# DispenserV2_0.net
KiCad netlist of a schematic drawn in EAGLE
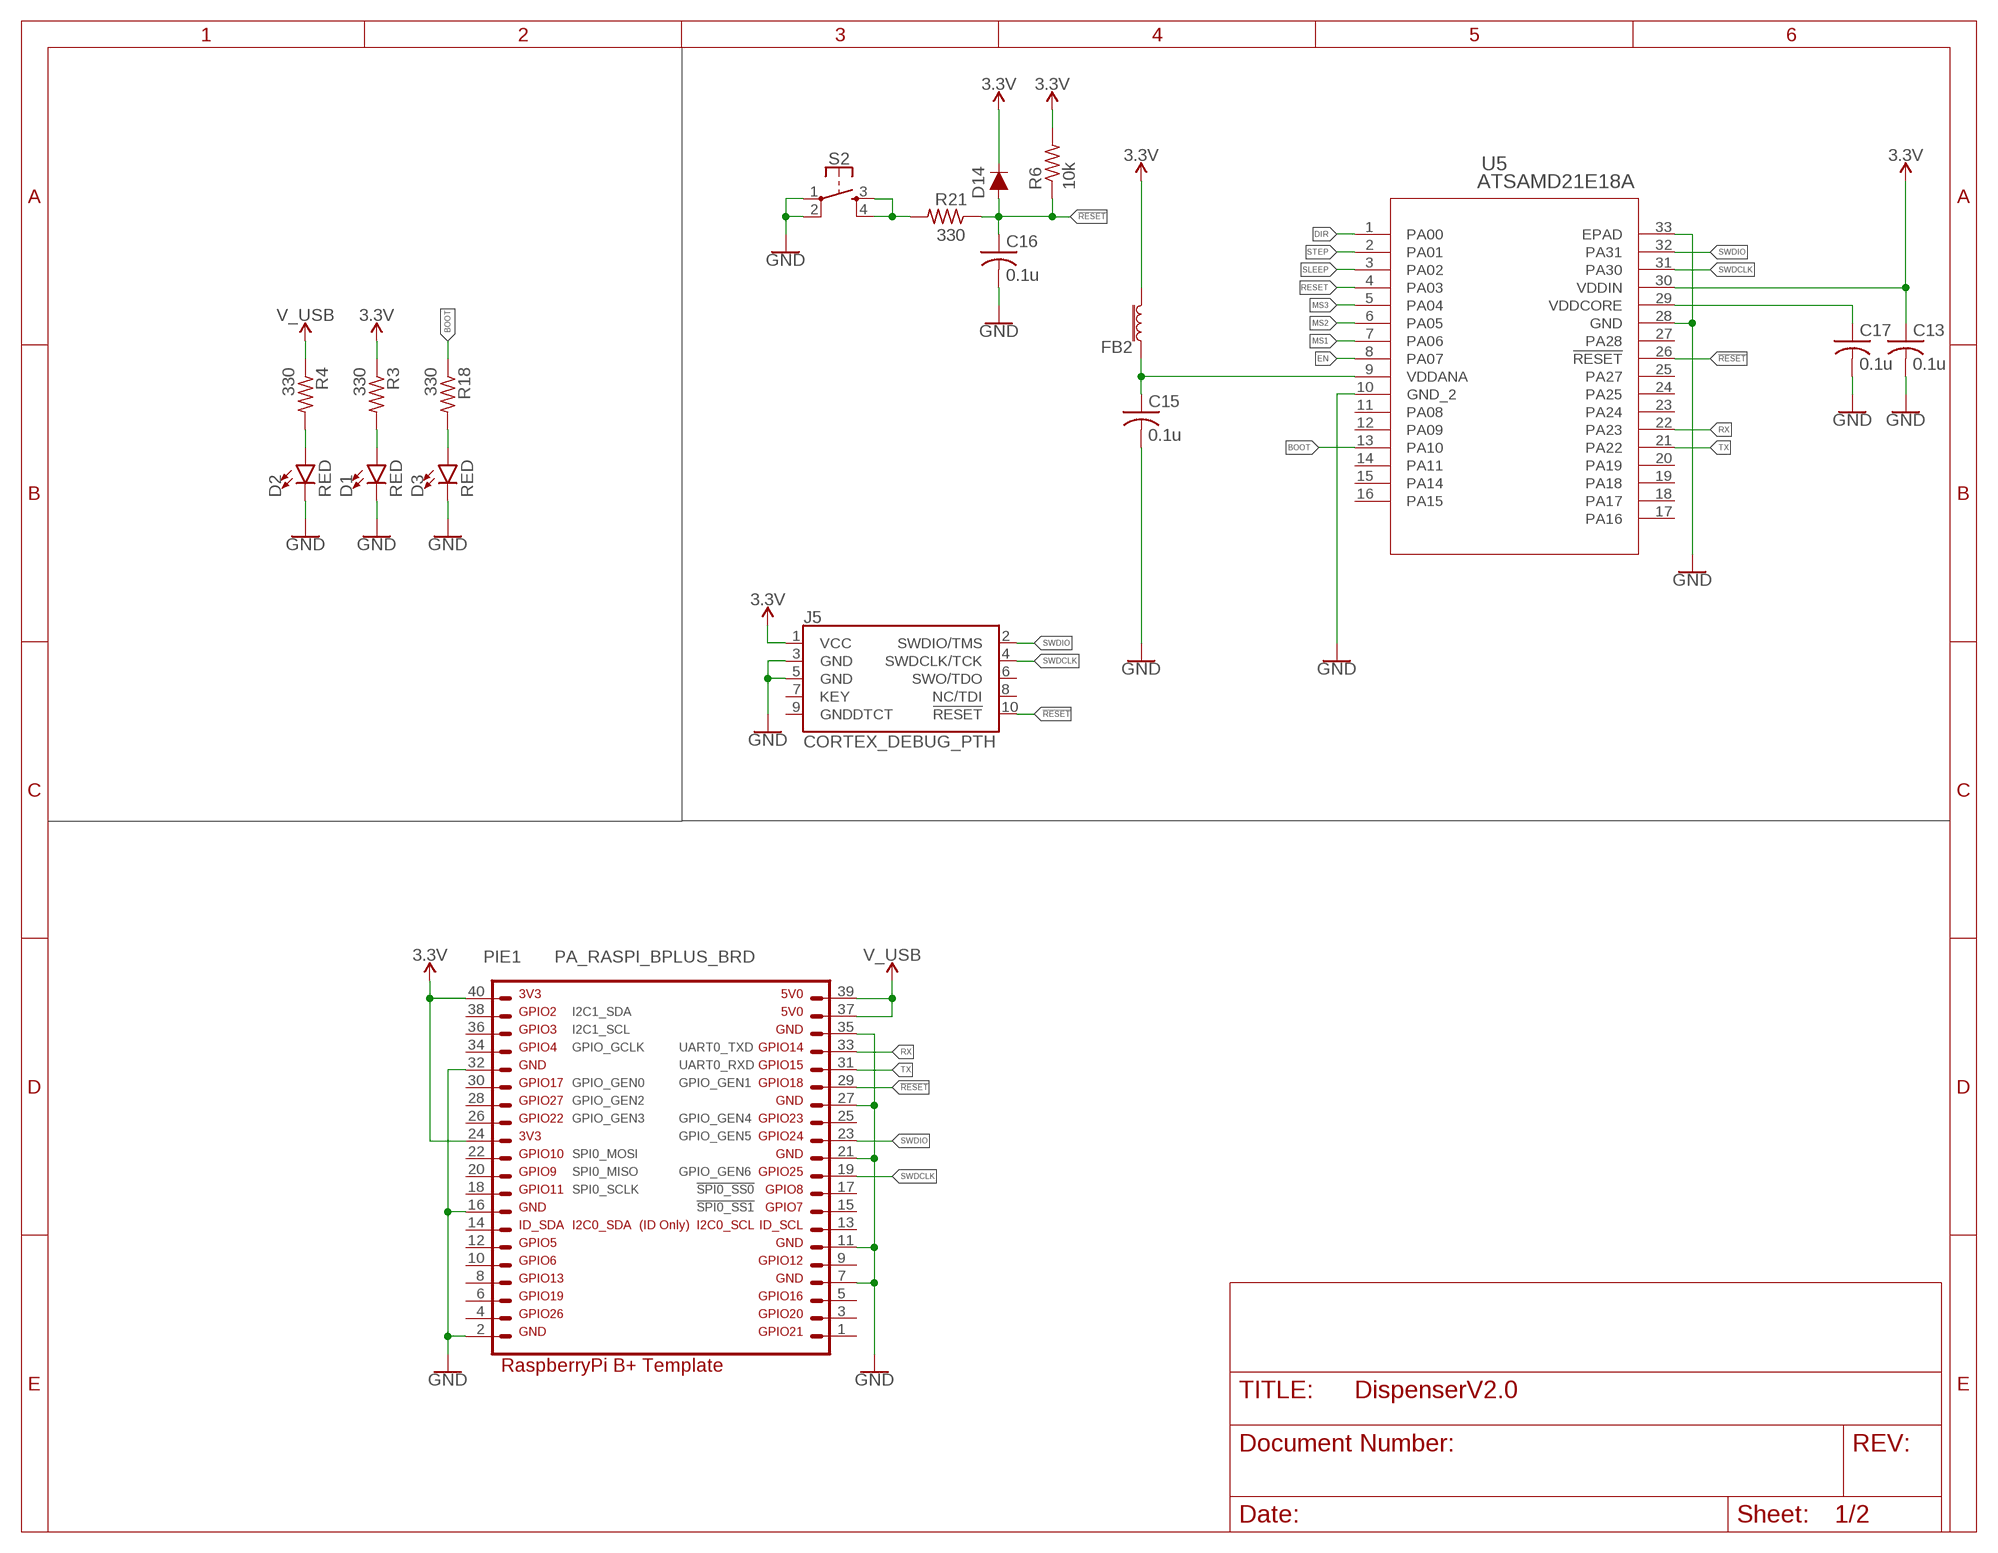
[diagram p0: schematic, sheet 1]
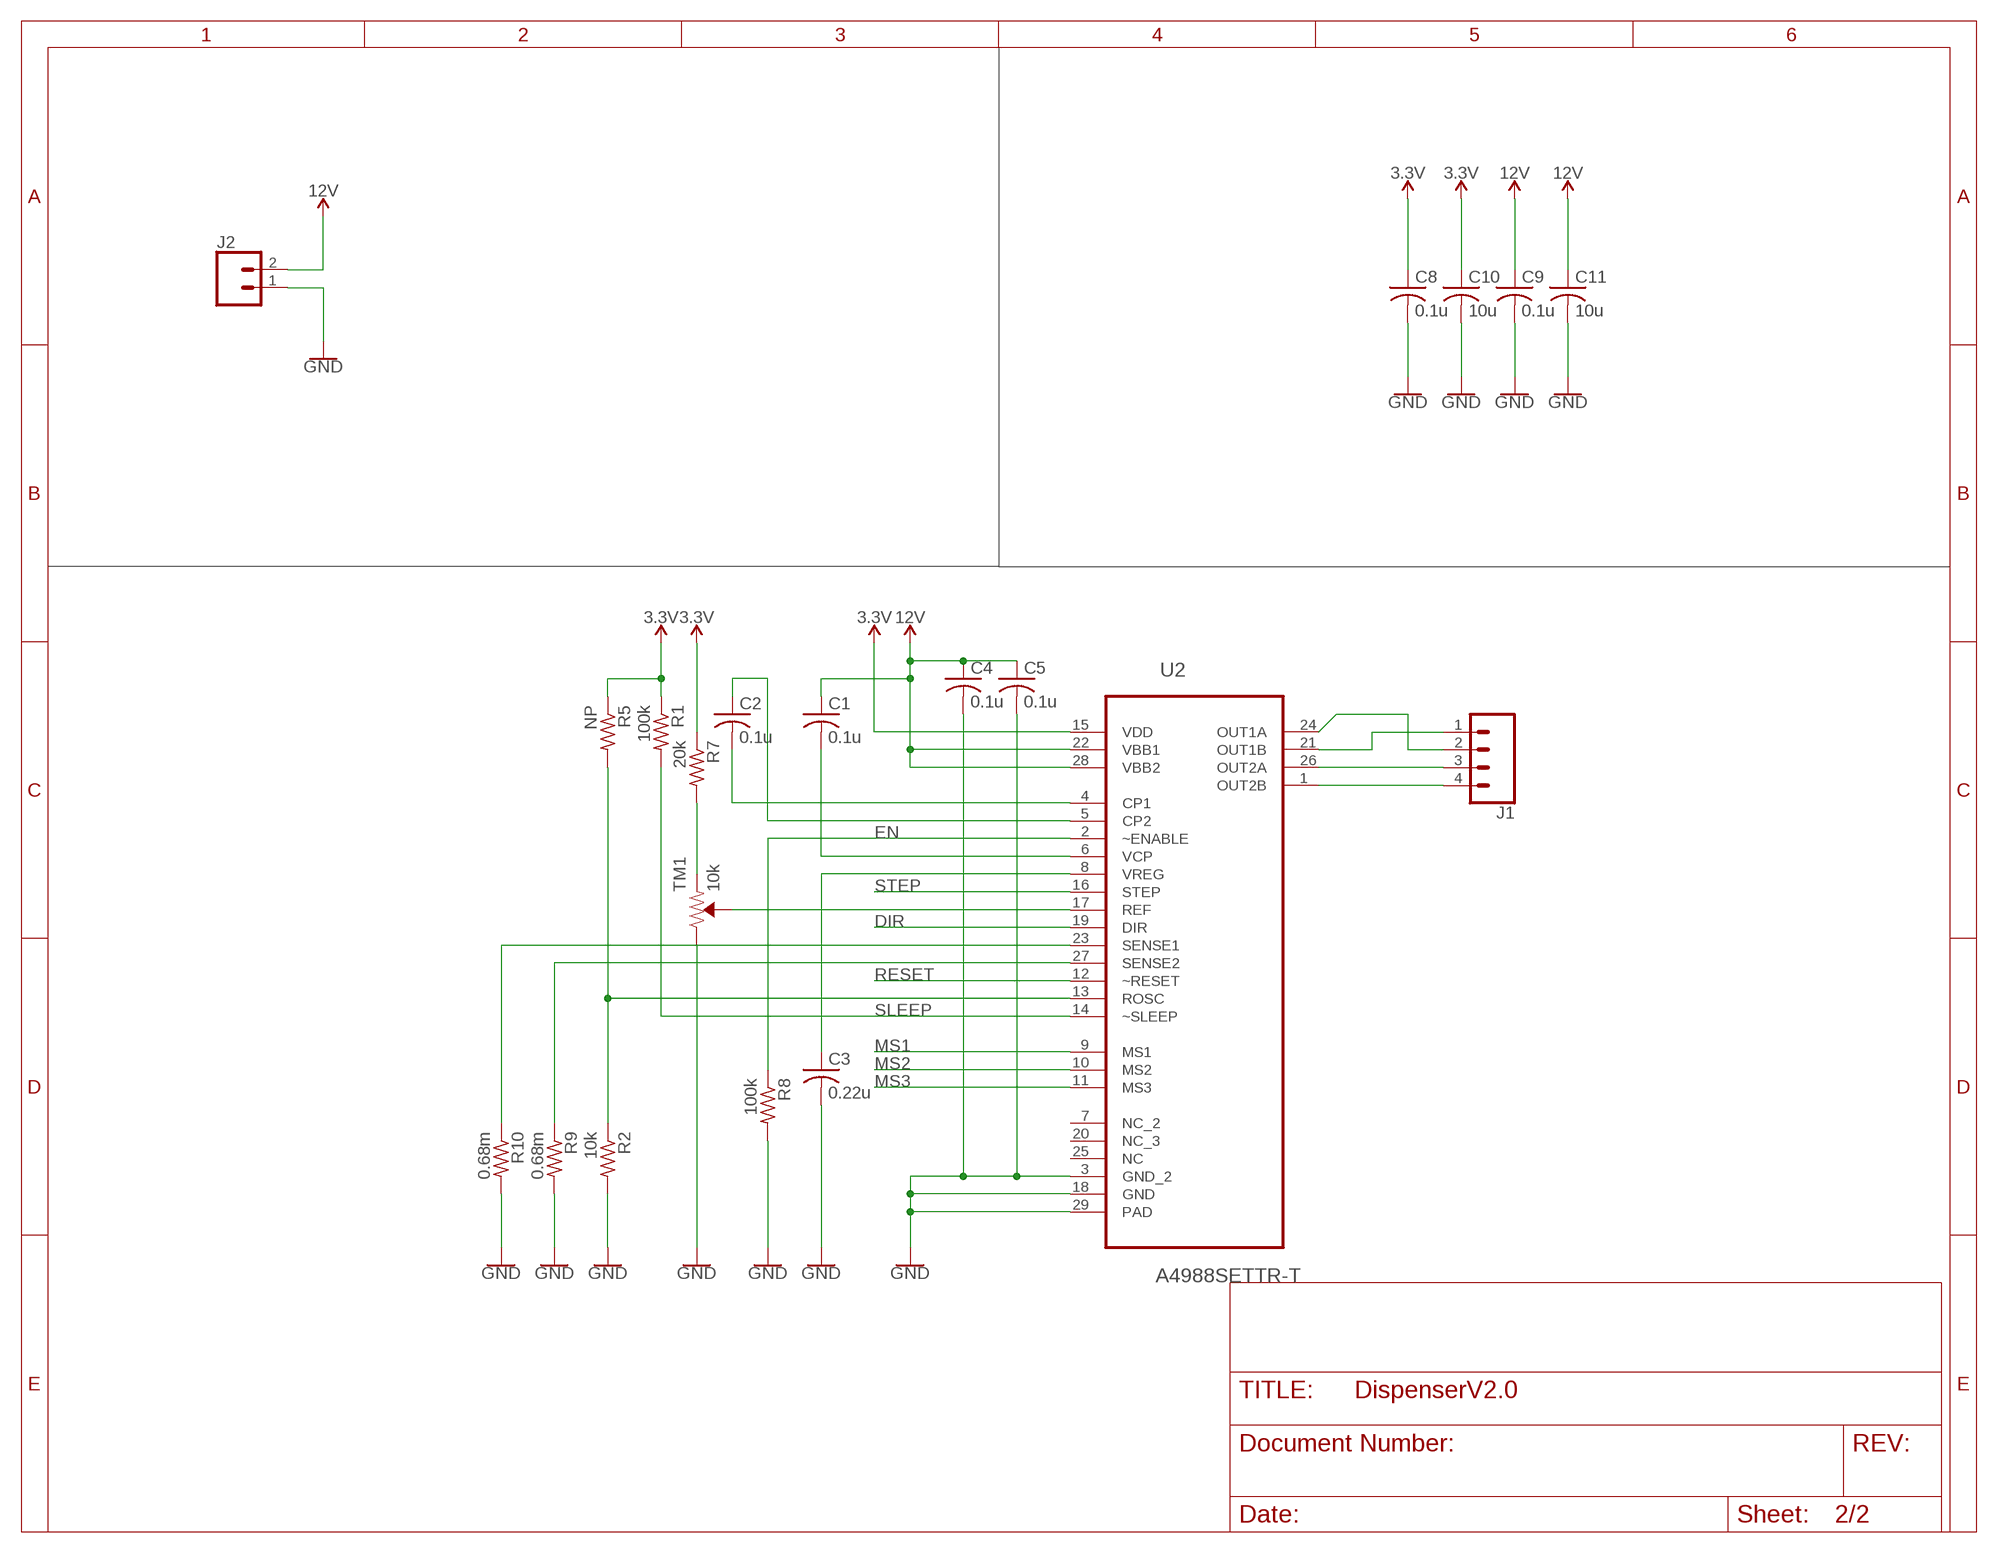
[diagram p1: schematic, sheet 2]

(export (version "E")
  (design (tool "Eeschema 10.0.6"))
  (components
    (comp (ref "C1")
      (value "0.1u")
      (footprint "eagle-import:C0402")
      (libsource (lib "eagle-import") (part "C-USC0402"))
    )
    (comp (ref "C2")
      (value "0.1u")
      (footprint "eagle-import:C0402")
      (libsource (lib "eagle-import") (part "C-USC0402"))
    )
    (comp (ref "C3")
      (value "0.22u")
      (footprint "eagle-import:C0402")
      (libsource (lib "eagle-import") (part "C-USC0402"))
    )
    (comp (ref "C4")
      (value "0.1u")
      (footprint "eagle-import:C0402")
      (libsource (lib "eagle-import") (part "C-USC0402"))
    )
    (comp (ref "C5")
      (value "0.1u")
      (footprint "eagle-import:C0402")
      (libsource (lib "eagle-import") (part "C-USC0402"))
    )
    (comp (ref "C8")
      (value "0.1u")
      (footprint "eagle-import:C0603")
      (libsource (lib "eagle-import") (part "adafruit_420_C-USC0603"))
    )
    (comp (ref "C9")
      (value "0.1u")
      (footprint "eagle-import:C0603")
      (libsource (lib "eagle-import") (part "adafruit_420_C-USC0603"))
    )
    (comp (ref "C10")
      (value "10u")
      (footprint "eagle-import:C1206")
      (libsource (lib "eagle-import") (part "C-USC1206"))
    )
    (comp (ref "C11")
      (value "10u")
      (footprint "eagle-import:C1206")
      (libsource (lib "eagle-import") (part "C-USC1206"))
    )
    (comp (ref "J1")
      (value "CONN_04")
      (footprint "eagle-import:1X04")
      (libsource (lib "eagle-import") (part "CONN_04"))
    )
    (comp (ref "J2")
      (value "CONN_023.5MM")
      (footprint "eagle-import:SCREWTERMINAL-3.5MM-2")
      (libsource (lib "eagle-import") (part "CONN_023.5MM"))
    )
    (comp (ref "R1")
      (value "100k")
      (footprint "eagle-import:R0402")
      (libsource (lib "eagle-import") (part "R-US_R0402"))
    )
    (comp (ref "R2")
      (value "10k")
      (footprint "eagle-import:R0402")
      (libsource (lib "eagle-import") (part "R-US_R0402"))
    )
    (comp (ref "R5")
      (value "NP")
      (footprint "eagle-import:R0402")
      (libsource (lib "eagle-import") (part "R-US_R0402"))
    )
    (comp (ref "R7")
      (value "20k")
      (footprint "eagle-import:R0402")
      (libsource (lib "eagle-import") (part "R-US_R0402"))
    )
    (comp (ref "R8")
      (value "100k")
      (footprint "eagle-import:R0402")
      (libsource (lib "eagle-import") (part "R-US_R0402"))
    )
    (comp (ref "R9")
      (value "0.68m")
      (footprint "eagle-import:R0805")
      (libsource (lib "eagle-import") (part "R-US_R0805"))
    )
    (comp (ref "R10")
      (value "0.68m")
      (footprint "eagle-import:R0805")
      (libsource (lib "eagle-import") (part "R-US_R0805"))
    )
    (comp (ref "TM1")
      (value "10k")
      (footprint "eagle-import:TRIMPOT-SMD-TC33X")
      (libsource (lib "eagle-import") (part "TRIMPOT-SMD-3MM-OPEN-1/10W-25%"))
    )
    (comp (ref "U2")
      (value "A4988SETTR-T")
      (footprint "eagle-import:QFN50P500X500X100-29N")
      (fields (field (name "MF") "Allegro MicroSystems LLC") (field (name "MP") "A4988SETTRT"))
      (libsource (lib "eagle-import") (part "A4988SETTR-T"))
    )
    (comp (ref "C13")
      (value "0.1u")
      (footprint "eagle-import:C0603K")
      (libsource (lib "eagle-import") (part "C-USC0603K"))
    )
    (comp (ref "C15")
      (value "0.1u")
      (footprint "eagle-import:C0603K")
      (libsource (lib "eagle-import") (part "C-USC0603K"))
    )
    (comp (ref "C16")
      (value "0.1u")
      (footprint "eagle-import:C0603K")
      (libsource (lib "eagle-import") (part "C-USC0603K"))
    )
    (comp (ref "C17")
      (value "0.1u")
      (footprint "eagle-import:C0603K")
      (libsource (lib "eagle-import") (part "C-USC0603K"))
    )
    (comp (ref "D1")
      (value "RED")
      (footprint "eagle-import:LED-0603")
      (libsource (lib "eagle-import") (part "LED-RED0603"))
    )
    (comp (ref "D2")
      (value "RED")
      (footprint "eagle-import:LED-0603")
      (libsource (lib "eagle-import") (part "LED-RED0603"))
    )
    (comp (ref "D3")
      (value "RED")
      (footprint "eagle-import:LED-0603")
      (libsource (lib "eagle-import") (part "LED-RED0603"))
    )
    (comp (ref "D14")
      (value "250mA/100V")
      (footprint "eagle-import:SOD-323")
      (libsource (lib "eagle-import") (part "DIODE-BAS16J"))
    )
    (comp (ref "FB2")
      (value "30Ω/1.8A")
      (footprint "eagle-import:0603")
      (libsource (lib "eagle-import") (part "FERRITE_BEAD-0603"))
    )
    (comp (ref "J5")
      (value "CORTEX_DEBUG_PTH")
      (footprint "eagle-import:2X5-PTH-1.27MM")
      (libsource (lib "eagle-import") (part "CORTEX_DEBUG_PTH"))
    )
    (comp (ref "PIE1")
      (value "PA_RASPI_BPLUS_BRD")
      (footprint "eagle-import:PA_RASPI_PLATE_BPLUS")
      (libsource (lib "eagle-import") (part "PA_RASPI_BPLUS_BRD"))
    )
    (comp (ref "R3")
      (value "330")
      (footprint "eagle-import:R0603")
      (libsource (lib "eagle-import") (part "R-US_R0603"))
    )
    (comp (ref "R4")
      (value "330")
      (footprint "eagle-import:R0603")
      (libsource (lib "eagle-import") (part "R-US_R0603"))
    )
    (comp (ref "R6")
      (value "10k")
      (footprint "eagle-import:R0603")
      (libsource (lib "eagle-import") (part "R-US_R0603"))
    )
    (comp (ref "R18")
      (value "330")
      (footprint "eagle-import:R0603")
      (libsource (lib "eagle-import") (part "R-US_R0603"))
    )
    (comp (ref "R21")
      (value "330")
      (footprint "eagle-import:R0603")
      (libsource (lib "eagle-import") (part "R-US_R0603"))
    )
    (comp (ref "S2")
      (value "MOMENTARY-SWITCH-SPST-2-SMD-5.2MM")
      (footprint "eagle-import:TACTILE_SWITCH_SMD_5.2MM")
      (libsource (lib "eagle-import") (part "MOMENTARY-SWITCH-SPST-2-SMD-5.2MM"))
    )
    (comp (ref "U5")
      (value "ATSAMD21E18A")
      (footprint "eagle-import:QFN32_5X5MC")
      (fields
        (field (name "MANUFACTURER_PART_NUMBER") "ATSAMD21E18A-MUT")
        (field (name "COPYRIGHT") "Copyright (C) 2018 Accelerated Designs. All rights reserved")
      )
      (libsource (lib "eagle-import") (part "ATSAMD21E18A-MUT"))
    )
  )
  (nets
    (net (code "1") (name "3.3V") (class "Default")
      (node (ref "C10") (pin "1") (pinfunction "1_1") (pintype "passive"))
      (node (ref "C13") (pin "1") (pinfunction "1_1") (pintype "passive"))
      (node (ref "C8") (pin "1") (pinfunction "1_1") (pintype "passive"))
      (node (ref "D14") (pin "C") (pinfunction "C_C") (pintype "passive"))
      (node (ref "FB2") (pin "2") (pinfunction "2_2") (pintype "passive"))
      (node (ref "J5") (pin "1") (pinfunction "VCC_1") (pintype "bidirectional"))
      (node (ref "PIE1") (pin "24") (pinfunction "24_24") (pintype "passive"))
      (node (ref "PIE1") (pin "40") (pinfunction "40_40") (pintype "passive"))
      (node (ref "R1") (pin "1") (pinfunction "1_1") (pintype "passive"))
      (node (ref "R3") (pin "1") (pinfunction "1_1") (pintype "passive"))
      (node (ref "R5") (pin "1") (pinfunction "1_1") (pintype "passive"))
      (node (ref "R6") (pin "2") (pinfunction "2_2") (pintype "passive"))
      (node (ref "R7") (pin "1") (pinfunction "1_1") (pintype "passive"))
      (node (ref "U2") (pin "15") (pinfunction "VDD_15") (pintype "power_in"))
      (node (ref "U5") (pin "30") (pinfunction "VDDIN_30") (pintype "power_in"))
    )
    (net (code "2") (name "12V") (class "Default")
      (node (ref "C1") (pin "1") (pinfunction "1_1") (pintype "passive"))
      (node (ref "C11") (pin "1") (pinfunction "1_1") (pintype "passive"))
      (node (ref "C4") (pin "1") (pinfunction "1_1") (pintype "passive"))
      (node (ref "C5") (pin "1") (pinfunction "1_1") (pintype "passive"))
      (node (ref "C9") (pin "1") (pinfunction "1_1") (pintype "passive"))
      (node (ref "J2") (pin "2") (pinfunction "2_2") (pintype "passive"))
      (node (ref "U2") (pin "22") (pinfunction "VBB1_22") (pintype "power_in"))
      (node (ref "U2") (pin "28") (pinfunction "VBB2_28") (pintype "power_in"))
    )
    (net (code "3") (name "BOOT") (class "Default")
      (node (ref "R18") (pin "1") (pinfunction "1_1") (pintype "passive"))
      (node (ref "U5") (pin "13") (pinfunction "PA10_13") (pintype "bidirectional"))
    )
    (net (code "4") (name "DIR") (class "Default")
      (node (ref "U2") (pin "19") (pinfunction "DIR_19") (pintype "input"))
      (node (ref "U5") (pin "1") (pinfunction "PA00_1") (pintype "bidirectional"))
    )
    (net (code "5") (name "EN") (class "Default")
      (node (ref "R8") (pin "1") (pinfunction "1_1") (pintype "passive"))
      (node (ref "U2") (pin "2") (pinfunction "~{ENABLE}_2") (pintype "input"))
      (node (ref "U5") (pin "8") (pinfunction "PA07_8") (pintype "bidirectional"))
    )
    (net (code "6") (name "GND") (class "Default")
      (node (ref "C10") (pin "2") (pinfunction "2_2") (pintype "passive"))
      (node (ref "C11") (pin "2") (pinfunction "2_2") (pintype "passive"))
      (node (ref "C13") (pin "2") (pinfunction "2_2") (pintype "passive"))
      (node (ref "C15") (pin "2") (pinfunction "2_2") (pintype "passive"))
      (node (ref "C16") (pin "2") (pinfunction "2_2") (pintype "passive"))
      (node (ref "C17") (pin "2") (pinfunction "2_2") (pintype "passive"))
      (node (ref "C3") (pin "2") (pinfunction "2_2") (pintype "passive"))
      (node (ref "C4") (pin "2") (pinfunction "2_2") (pintype "passive"))
      (node (ref "C5") (pin "2") (pinfunction "2_2") (pintype "passive"))
      (node (ref "C8") (pin "2") (pinfunction "2_2") (pintype "passive"))
      (node (ref "C9") (pin "2") (pinfunction "2_2") (pintype "passive"))
      (node (ref "D1") (pin "C") (pinfunction "C_C") (pintype "passive"))
      (node (ref "D2") (pin "C") (pinfunction "C_C") (pintype "passive"))
      (node (ref "D3") (pin "C") (pinfunction "C_C") (pintype "passive"))
      (node (ref "J2") (pin "1") (pinfunction "1_1") (pintype "passive"))
      (node (ref "J5") (pin "3") (pinfunction "GND_3") (pintype "bidirectional"))
      (node (ref "J5") (pin "5") (pinfunction "GND_5") (pintype "bidirectional"))
      (node (ref "PIE1") (pin "11") (pinfunction "11_11") (pintype "passive"))
      (node (ref "PIE1") (pin "16") (pinfunction "16_16") (pintype "passive"))
      (node (ref "PIE1") (pin "2") (pinfunction "2_2") (pintype "passive"))
      (node (ref "PIE1") (pin "21") (pinfunction "21_21") (pintype "passive"))
      (node (ref "PIE1") (pin "27") (pinfunction "27_27") (pintype "passive"))
      (node (ref "PIE1") (pin "32") (pinfunction "32_32") (pintype "passive"))
      (node (ref "PIE1") (pin "35") (pinfunction "35_35") (pintype "passive"))
      (node (ref "PIE1") (pin "7") (pinfunction "7_7") (pintype "passive"))
      (node (ref "R10") (pin "2") (pinfunction "2_2") (pintype "passive"))
      (node (ref "R2") (pin "2") (pinfunction "2_2") (pintype "passive"))
      (node (ref "R8") (pin "2") (pinfunction "2_2") (pintype "passive"))
      (node (ref "R9") (pin "2") (pinfunction "2_2") (pintype "passive"))
      (node (ref "S2") (pin "1") (pinfunction "1_1") (pintype "passive"))
      (node (ref "S2") (pin "2") (pinfunction "2_2") (pintype "passive"))
      (node (ref "TM1") (pin "1") (pinfunction "CW_1") (pintype "passive"))
      (node (ref "U2") (pin "18") (pinfunction "GND_18") (pintype "passive"))
      (node (ref "U2") (pin "29") (pinfunction "PAD_29") (pintype "passive"))
      (node (ref "U2") (pin "3") (pinfunction "GND_2_3") (pintype "passive"))
      (node (ref "U5") (pin "10") (pinfunction "GND_2_10") (pintype "passive"))
      (node (ref "U5") (pin "28") (pinfunction "GND_28") (pintype "passive"))
      (node (ref "U5") (pin "33") (pinfunction "EPAD_33") (pintype "passive"))
    )
    (net (code "7") (name "MS1") (class "Default")
      (node (ref "U2") (pin "9") (pinfunction "MS1_9") (pintype "input"))
      (node (ref "U5") (pin "7") (pinfunction "PA06_7") (pintype "bidirectional"))
    )
    (net (code "8") (name "MS2") (class "Default")
      (node (ref "U2") (pin "10") (pinfunction "MS2_10") (pintype "input"))
      (node (ref "U5") (pin "6") (pinfunction "PA05_6") (pintype "bidirectional"))
    )
    (net (code "9") (name "MS3") (class "Default")
      (node (ref "U2") (pin "11") (pinfunction "MS3_11") (pintype "input"))
      (node (ref "U5") (pin "5") (pinfunction "PA04_5") (pintype "bidirectional"))
    )
    (net (code "10") (name "Net-(D1-PadA)") (class "Default")
      (node (ref "D1") (pin "A") (pinfunction "A_A") (pintype "passive"))
      (node (ref "R3") (pin "2") (pinfunction "2_2") (pintype "passive"))
    )
    (net (code "11") (name "Net-(D2-PadA)") (class "Default")
      (node (ref "D2") (pin "A") (pinfunction "A_A") (pintype "passive"))
      (node (ref "R4") (pin "2") (pinfunction "2_2") (pintype "passive"))
    )
    (net (code "12") (name "Net-(D3-PadA)") (class "Default")
      (node (ref "D3") (pin "A") (pinfunction "A_A") (pintype "passive"))
      (node (ref "R18") (pin "2") (pinfunction "2_2") (pintype "passive"))
    )
    (net (code "13") (name "Net-(R21-Pad2)") (class "Default")
      (node (ref "R21") (pin "2") (pinfunction "2_2") (pintype "passive"))
      (node (ref "S2") (pin "3") (pinfunction "3_3") (pintype "passive"))
      (node (ref "S2") (pin "4") (pinfunction "4_4") (pintype "passive"))
    )
    (net (code "14") (name "Net-(TM1-CCW)") (class "Default")
      (node (ref "R7") (pin "2") (pinfunction "2_2") (pintype "passive"))
      (node (ref "TM1") (pin "3") (pinfunction "CCW_3") (pintype "passive"))
    )
    (net (code "15") (name "Net-(TM1-WIPER)") (class "Default")
      (node (ref "TM1") (pin "2") (pinfunction "WIPER_2") (pintype "passive"))
      (node (ref "U2") (pin "17") (pinfunction "REF_17") (pintype "input"))
    )
    (net (code "16") (name "Net-(U2-CP1)") (class "Default")
      (node (ref "C2") (pin "2") (pinfunction "2_2") (pintype "passive"))
      (node (ref "U2") (pin "4") (pinfunction "CP1_4") (pintype "passive"))
    )
    (net (code "17") (name "Net-(U2-CP2)") (class "Default")
      (node (ref "C2") (pin "1") (pinfunction "1_1") (pintype "passive"))
      (node (ref "U2") (pin "5") (pinfunction "CP2_5") (pintype "passive"))
    )
    (net (code "18") (name "Net-(U2-OUT1A)") (class "Default")
      (node (ref "J1") (pin "2") (pinfunction "2_2") (pintype "passive"))
      (node (ref "U2") (pin "24") (pinfunction "OUT1A_24") (pintype "output"))
    )
    (net (code "19") (name "Net-(U2-OUT1B)") (class "Default")
      (node (ref "J1") (pin "1") (pinfunction "1_1") (pintype "passive"))
      (node (ref "U2") (pin "21") (pinfunction "OUT1B_21") (pintype "output"))
    )
    (net (code "20") (name "Net-(U2-OUT2A)") (class "Default")
      (node (ref "J1") (pin "3") (pinfunction "3_3") (pintype "passive"))
      (node (ref "U2") (pin "26") (pinfunction "OUT2A_26") (pintype "output"))
    )
    (net (code "21") (name "Net-(U2-OUT2B)") (class "Default")
      (node (ref "J1") (pin "4") (pinfunction "4_4") (pintype "passive"))
      (node (ref "U2") (pin "1") (pinfunction "OUT2B_1") (pintype "output"))
    )
    (net (code "22") (name "Net-(U2-ROSC)") (class "Default")
      (node (ref "R2") (pin "1") (pinfunction "1_1") (pintype "passive"))
      (node (ref "R5") (pin "2") (pinfunction "2_2") (pintype "passive"))
      (node (ref "U2") (pin "13") (pinfunction "ROSC_13") (pintype "input"))
    )
    (net (code "23") (name "Net-(U2-SENSE1)") (class "Default")
      (node (ref "R10") (pin "1") (pinfunction "1_1") (pintype "passive"))
      (node (ref "U2") (pin "23") (pinfunction "SENSE1_23") (pintype "input"))
    )
    (net (code "24") (name "Net-(U2-SENSE2)") (class "Default")
      (node (ref "R9") (pin "1") (pinfunction "1_1") (pintype "passive"))
      (node (ref "U2") (pin "27") (pinfunction "SENSE2_27") (pintype "input"))
    )
    (net (code "25") (name "Net-(U2-VCP)") (class "Default")
      (node (ref "C1") (pin "2") (pinfunction "2_2") (pintype "passive"))
      (node (ref "U2") (pin "6") (pinfunction "VCP_6") (pintype "passive"))
    )
    (net (code "26") (name "Net-(U2-VREG)") (class "Default")
      (node (ref "C3") (pin "1") (pinfunction "1_1") (pintype "passive"))
      (node (ref "U2") (pin "8") (pinfunction "VREG_8") (pintype "passive"))
    )
    (net (code "27") (name "Net-(U5-VDDANA)") (class "Default")
      (node (ref "C15") (pin "1") (pinfunction "1_1") (pintype "passive"))
      (node (ref "FB2") (pin "1") (pinfunction "1_1") (pintype "passive"))
      (node (ref "U5") (pin "9") (pinfunction "VDDANA_9") (pintype "power_in"))
    )
    (net (code "28") (name "Net-(U5-VDDCORE)") (class "Default")
      (node (ref "C17") (pin "1") (pinfunction "1_1") (pintype "passive"))
      (node (ref "U5") (pin "29") (pinfunction "VDDCORE_29") (pintype "power_in"))
    )
    (net (code "29") (name "RESET") (class "Default")
      (node (ref "U2") (pin "12") (pinfunction "~{RESET}_12") (pintype "input"))
      (node (ref "U5") (pin "4") (pinfunction "PA03_4") (pintype "bidirectional"))
    )
    (net (code "30") (name "RX") (class "Default")
      (node (ref "PIE1") (pin "33") (pinfunction "33_33") (pintype "passive"))
      (node (ref "U5") (pin "22") (pinfunction "PA23_22") (pintype "bidirectional"))
    )
    (net (code "31") (name "SLEEP") (class "Default")
      (node (ref "R1") (pin "2") (pinfunction "2_2") (pintype "passive"))
      (node (ref "U2") (pin "14") (pinfunction "~{SLEEP}_14") (pintype "input"))
      (node (ref "U5") (pin "3") (pinfunction "PA02_3") (pintype "bidirectional"))
    )
    (net (code "32") (name "STEP") (class "Default")
      (node (ref "U2") (pin "16") (pinfunction "STEP_16") (pintype "input"))
      (node (ref "U5") (pin "2") (pinfunction "PA01_2") (pintype "bidirectional"))
    )
    (net (code "33") (name "SWDCLK") (class "Default")
      (node (ref "J5") (pin "4") (pinfunction "SWDCLK/TCK_4") (pintype "bidirectional"))
      (node (ref "PIE1") (pin "19") (pinfunction "19_19") (pintype "passive"))
      (node (ref "U5") (pin "31") (pinfunction "PA30_31") (pintype "bidirectional"))
    )
    (net (code "34") (name "SWDIO") (class "Default")
      (node (ref "J5") (pin "2") (pinfunction "SWDIO/TMS_2") (pintype "bidirectional"))
      (node (ref "PIE1") (pin "23") (pinfunction "23_23") (pintype "passive"))
      (node (ref "U5") (pin "32") (pinfunction "PA31_32") (pintype "bidirectional"))
    )
    (net (code "35") (name "TX") (class "Default")
      (node (ref "PIE1") (pin "31") (pinfunction "31_31") (pintype "passive"))
      (node (ref "U5") (pin "21") (pinfunction "PA22_21") (pintype "bidirectional"))
    )
    (net (code "36") (name "V_USB") (class "Default")
      (node (ref "PIE1") (pin "37") (pinfunction "37_37") (pintype "passive"))
      (node (ref "PIE1") (pin "39") (pinfunction "39_39") (pintype "passive"))
      (node (ref "R4") (pin "1") (pinfunction "1_1") (pintype "passive"))
    )
    (net (code "37") (name "unconnected-(J5-GNDDTCT-Pad9)") (class "Default")
      (node (ref "J5") (pin "9") (pinfunction "GNDDTCT_9") (pintype "bidirectional"))
    )
    (net (code "38") (name "unconnected-(J5-KEY-Pad7)") (class "Default")
      (node (ref "J5") (pin "7") (pinfunction "KEY_7") (pintype "bidirectional"))
    )
    (net (code "39") (name "unconnected-(J5-NC{slash}TDI-Pad8)") (class "Default")
      (node (ref "J5") (pin "8") (pinfunction "NC/TDI_8") (pintype "bidirectional"))
    )
    (net (code "40") (name "unconnected-(J5-SWO{slash}TDO-Pad6)") (class "Default")
      (node (ref "J5") (pin "6") (pinfunction "SWO/TDO_6") (pintype "bidirectional"))
    )
    (net (code "41") (name "unconnected-(PIE1-Pad1)") (class "Default")
      (node (ref "PIE1") (pin "1") (pinfunction "1_1") (pintype "passive"))
    )
    (net (code "42") (name "unconnected-(PIE1-Pad3)") (class "Default")
      (node (ref "PIE1") (pin "3") (pinfunction "3_3") (pintype "passive"))
    )
    (net (code "43") (name "unconnected-(PIE1-Pad4)") (class "Default")
      (node (ref "PIE1") (pin "4") (pinfunction "4_4") (pintype "passive"))
    )
    (net (code "44") (name "unconnected-(PIE1-Pad5)") (class "Default")
      (node (ref "PIE1") (pin "5") (pinfunction "5_5") (pintype "passive"))
    )
    (net (code "45") (name "unconnected-(PIE1-Pad6)") (class "Default")
      (node (ref "PIE1") (pin "6") (pinfunction "6_6") (pintype "passive"))
    )
    (net (code "46") (name "unconnected-(PIE1-Pad8)") (class "Default")
      (node (ref "PIE1") (pin "8") (pinfunction "8_8") (pintype "passive"))
    )
    (net (code "47") (name "unconnected-(PIE1-Pad9)") (class "Default")
      (node (ref "PIE1") (pin "9") (pinfunction "9_9") (pintype "passive"))
    )
    (net (code "48") (name "unconnected-(PIE1-Pad10)") (class "Default")
      (node (ref "PIE1") (pin "10") (pinfunction "10_10") (pintype "passive"))
    )
    (net (code "49") (name "unconnected-(PIE1-Pad12)") (class "Default")
      (node (ref "PIE1") (pin "12") (pinfunction "12_12") (pintype "passive"))
    )
    (net (code "50") (name "unconnected-(PIE1-Pad13)") (class "Default")
      (node (ref "PIE1") (pin "13") (pinfunction "13_13") (pintype "passive"))
    )
    (net (code "51") (name "unconnected-(PIE1-Pad14)") (class "Default")
      (node (ref "PIE1") (pin "14") (pinfunction "14_14") (pintype "passive"))
    )
    (net (code "52") (name "unconnected-(PIE1-Pad15)") (class "Default")
      (node (ref "PIE1") (pin "15") (pinfunction "15_15") (pintype "passive"))
    )
    (net (code "53") (name "unconnected-(PIE1-Pad17)") (class "Default")
      (node (ref "PIE1") (pin "17") (pinfunction "17_17") (pintype "passive"))
    )
    (net (code "54") (name "unconnected-(PIE1-Pad18)") (class "Default")
      (node (ref "PIE1") (pin "18") (pinfunction "18_18") (pintype "passive"))
    )
    (net (code "55") (name "unconnected-(PIE1-Pad20)") (class "Default")
      (node (ref "PIE1") (pin "20") (pinfunction "20_20") (pintype "passive"))
    )
    (net (code "56") (name "unconnected-(PIE1-Pad22)") (class "Default")
      (node (ref "PIE1") (pin "22") (pinfunction "22_22") (pintype "passive"))
    )
    (net (code "57") (name "unconnected-(PIE1-Pad25)") (class "Default")
      (node (ref "PIE1") (pin "25") (pinfunction "25_25") (pintype "passive"))
    )
    (net (code "58") (name "unconnected-(PIE1-Pad26)") (class "Default")
      (node (ref "PIE1") (pin "26") (pinfunction "26_26") (pintype "passive"))
    )
    (net (code "59") (name "unconnected-(PIE1-Pad28)") (class "Default")
      (node (ref "PIE1") (pin "28") (pinfunction "28_28") (pintype "passive"))
    )
    (net (code "60") (name "unconnected-(PIE1-Pad30)") (class "Default")
      (node (ref "PIE1") (pin "30") (pinfunction "30_30") (pintype "passive"))
    )
    (net (code "61") (name "unconnected-(PIE1-Pad34)") (class "Default")
      (node (ref "PIE1") (pin "34") (pinfunction "34_34") (pintype "passive"))
    )
    (net (code "62") (name "unconnected-(PIE1-Pad36)") (class "Default")
      (node (ref "PIE1") (pin "36") (pinfunction "36_36") (pintype "passive"))
    )
    (net (code "63") (name "unconnected-(PIE1-Pad38)") (class "Default")
      (node (ref "PIE1") (pin "38") (pinfunction "38_38") (pintype "passive"))
    )
    (net (code "64") (name "unconnected-(U2-NC-Pad25)") (class "Default")
      (node (ref "U2") (pin "25") (pinfunction "NC_25") (pintype "no_connect"))
    )
    (net (code "65") (name "unconnected-(U2-NC_2-Pad7)") (class "Default")
      (node (ref "U2") (pin "7") (pinfunction "NC_2_7") (pintype "no_connect"))
    )
    (net (code "66") (name "unconnected-(U2-NC_3-Pad20)") (class "Default")
      (node (ref "U2") (pin "20") (pinfunction "NC_3_20") (pintype "no_connect"))
    )
    (net (code "67") (name "unconnected-(U5-PA08-Pad11)") (class "Default")
      (node (ref "U5") (pin "11") (pinfunction "PA08_11") (pintype "bidirectional"))
    )
    (net (code "68") (name "unconnected-(U5-PA09-Pad12)") (class "Default")
      (node (ref "U5") (pin "12") (pinfunction "PA09_12") (pintype "bidirectional"))
    )
    (net (code "69") (name "unconnected-(U5-PA11-Pad14)") (class "Default")
      (node (ref "U5") (pin "14") (pinfunction "PA11_14") (pintype "bidirectional"))
    )
    (net (code "70") (name "unconnected-(U5-PA14-Pad15)") (class "Default")
      (node (ref "U5") (pin "15") (pinfunction "PA14_15") (pintype "bidirectional"))
    )
    (net (code "71") (name "unconnected-(U5-PA15-Pad16)") (class "Default")
      (node (ref "U5") (pin "16") (pinfunction "PA15_16") (pintype "bidirectional"))
    )
    (net (code "72") (name "unconnected-(U5-PA16-Pad17)") (class "Default")
      (node (ref "U5") (pin "17") (pinfunction "PA16_17") (pintype "bidirectional"))
    )
    (net (code "73") (name "unconnected-(U5-PA17-Pad18)") (class "Default")
      (node (ref "U5") (pin "18") (pinfunction "PA17_18") (pintype "bidirectional"))
    )
    (net (code "74") (name "unconnected-(U5-PA18-Pad19)") (class "Default")
      (node (ref "U5") (pin "19") (pinfunction "PA18_19") (pintype "bidirectional"))
    )
    (net (code "75") (name "unconnected-(U5-PA19-Pad20)") (class "Default")
      (node (ref "U5") (pin "20") (pinfunction "PA19_20") (pintype "bidirectional"))
    )
    (net (code "76") (name "unconnected-(U5-PA24-Pad23)") (class "Default")
      (node (ref "U5") (pin "23") (pinfunction "PA24_23") (pintype "bidirectional"))
    )
    (net (code "77") (name "unconnected-(U5-PA25-Pad24)") (class "Default")
      (node (ref "U5") (pin "24") (pinfunction "PA25_24") (pintype "bidirectional"))
    )
    (net (code "78") (name "unconnected-(U5-PA27-Pad25)") (class "Default")
      (node (ref "U5") (pin "25") (pinfunction "PA27_25") (pintype "bidirectional"))
    )
    (net (code "79") (name "unconnected-(U5-PA28-Pad27)") (class "Default")
      (node (ref "U5") (pin "27") (pinfunction "PA28_27") (pintype "bidirectional"))
    )
    (net (code "80") (name "~{RESET}") (class "Default")
      (node (ref "C16") (pin "1") (pinfunction "1_1") (pintype "passive"))
      (node (ref "D14") (pin "A") (pinfunction "A_A") (pintype "passive"))
      (node (ref "J5") (pin "10") (pinfunction "~{RESET}_10") (pintype "bidirectional"))
      (node (ref "PIE1") (pin "29") (pinfunction "29_29") (pintype "passive"))
      (node (ref "R21") (pin "1") (pinfunction "1_1") (pintype "passive"))
      (node (ref "R6") (pin "1") (pinfunction "1_1") (pintype "passive"))
      (node (ref "U5") (pin "26") (pinfunction "~{RESET}_26") (pintype "passive"))
    )
  )
)
